# CAR_phase_1_schematic_design.net
KiCad netlist of a schematic drawn in EAGLE
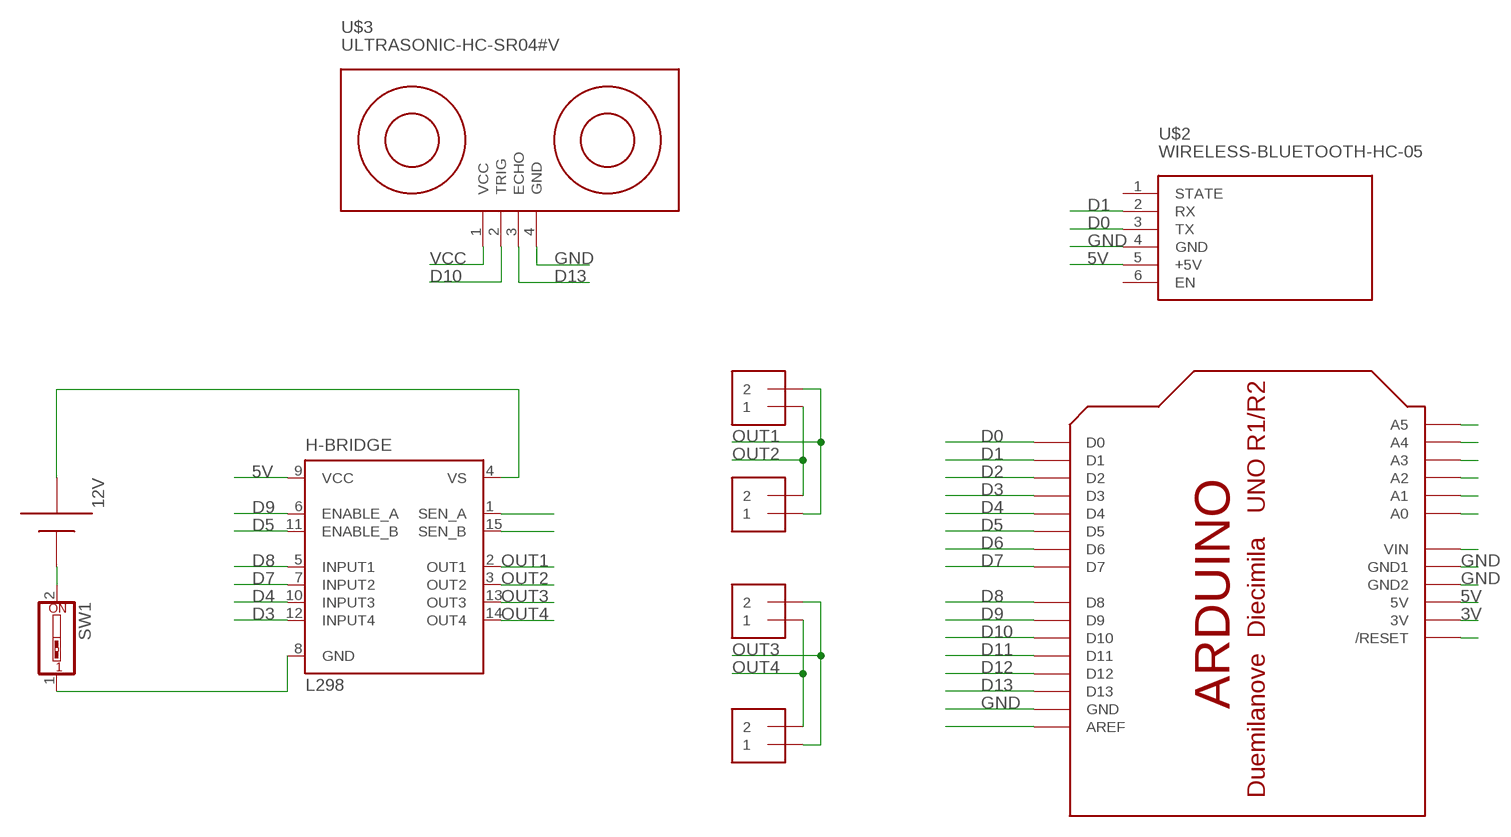
[diagram p0: schematic, sheet 1]

(export (version "E")
  (design (tool "Eeschema 10.0.6"))
  (components
    (comp (ref "12V")
      (value "AAA")
      (footprint "eagle-import:12BH412")
      (libsource (lib "eagle-import") (part "AAA"))
    )
    (comp (ref "H-BRIDGE")
      (value "L298")
      (footprint "eagle-import:MULTIWATT-15")
      (fields (field (name "MPN") "L298N"))
      (libsource (lib "eagle-import") (part "L298"))
    )
    (comp (ref "MOTOA1")
      (value "1X2-3.5MM")
      (footprint "eagle-import:1X2-3.5MM")
      (libsource (lib "eagle-import") (part "1X2-3.5MM"))
    )
    (comp (ref "MOTORA2")
      (value "1X2-3.5MM")
      (footprint "eagle-import:1X2-3.5MM")
      (libsource (lib "eagle-import") (part "1X2-3.5MM"))
    )
    (comp (ref "MOTORB1")
      (value "1X2-3.5MM")
      (footprint "eagle-import:1X2-3.5MM")
      (libsource (lib "eagle-import") (part "1X2-3.5MM"))
    )
    (comp (ref "MOTORB2")
      (value "1X2-3.5MM")
      (footprint "eagle-import:1X2-3.5MM")
      (libsource (lib "eagle-import") (part "1X2-3.5MM"))
    )
    (comp (ref "SW1")
      (value "SW_DIP-1")
      (footprint "eagle-import:EDG-01")
      (libsource (lib "eagle-import") (part "SW_DIP-1"))
    )
    (comp (ref "U$1")
      (value "ARDUINO-NOHOLE")
      (footprint "eagle-import:ARDUINO-NOHOLE")
      (libsource (lib "eagle-import") (part "ARDUINO-NOHOLE"))
    )
    (comp (ref "U$2")
      (value "WIRELESS-BLUETOOTH-HC-05")
      (footprint "eagle-import:WIRELESS-BLUETOOTH-HC-05")
      (libsource (lib "eagle-import") (part "WIRELESS-BLUETOOTH-HC-05"))
    )
    (comp (ref "U$3")
      (value "ULTRASONIC-HC-SR04#V")
      (footprint "eagle-import:ULTRASONIC-HC-SR04#V")
      (libsource (lib "eagle-import") (part "ULTRASONIC-HC-SR04#V"))
    )
  )
  (nets
    (net (code "1") (name "/3V") (class "Default")
      (node (ref "U$1") (pin "3V") (pinfunction "3V_3V") (pintype "power_in"))
    )
    (net (code "2") (name "/5V") (class "Default")
      (node (ref "H-BRIDGE") (pin "9") (pinfunction "VCC_9") (pintype "power_in"))
      (node (ref "U$1") (pin "5V") (pinfunction "5V_5V") (pintype "power_in"))
      (node (ref "U$2") (pin "5") (pinfunction "+5V_5") (pintype "power_in"))
    )
    (net (code "3") (name "/D0") (class "Default")
      (node (ref "U$1") (pin "D0") (pinfunction "D0_D0") (pintype "bidirectional"))
      (node (ref "U$2") (pin "3") (pinfunction "TX_3") (pintype "bidirectional"))
    )
    (net (code "4") (name "/D1") (class "Default")
      (node (ref "U$1") (pin "D1") (pinfunction "D1_D1") (pintype "bidirectional"))
      (node (ref "U$2") (pin "2") (pinfunction "RX_2") (pintype "bidirectional"))
    )
    (net (code "5") (name "/D2") (class "Default")
      (node (ref "U$1") (pin "D2") (pinfunction "D2_D2") (pintype "bidirectional"))
    )
    (net (code "6") (name "/D3") (class "Default")
      (node (ref "H-BRIDGE") (pin "12") (pinfunction "INPUT4_12") (pintype "input"))
      (node (ref "U$1") (pin "D3") (pinfunction "D3_D3") (pintype "bidirectional"))
    )
    (net (code "7") (name "/D4") (class "Default")
      (node (ref "H-BRIDGE") (pin "10") (pinfunction "INPUT3_10") (pintype "input"))
      (node (ref "U$1") (pin "D4") (pinfunction "D4_D4") (pintype "bidirectional"))
    )
    (net (code "8") (name "/D5") (class "Default")
      (node (ref "H-BRIDGE") (pin "11") (pinfunction "ENABLE_B_11") (pintype "input"))
      (node (ref "U$1") (pin "D5") (pinfunction "D5_D5") (pintype "bidirectional"))
    )
    (net (code "9") (name "/D6") (class "Default")
      (node (ref "U$1") (pin "D6") (pinfunction "D6_D6") (pintype "bidirectional"))
    )
    (net (code "10") (name "/D7") (class "Default")
      (node (ref "H-BRIDGE") (pin "7") (pinfunction "INPUT2_7") (pintype "input"))
      (node (ref "U$1") (pin "D7") (pinfunction "D7_D7") (pintype "bidirectional"))
    )
    (net (code "11") (name "/D8") (class "Default")
      (node (ref "H-BRIDGE") (pin "5") (pinfunction "INPUT1_5") (pintype "input"))
      (node (ref "U$1") (pin "D8") (pinfunction "D8_D8") (pintype "bidirectional"))
    )
    (net (code "12") (name "/D9") (class "Default")
      (node (ref "H-BRIDGE") (pin "6") (pinfunction "ENABLE_A_6") (pintype "input"))
      (node (ref "U$1") (pin "D9") (pinfunction "D9_D9") (pintype "bidirectional"))
    )
    (net (code "13") (name "/D10") (class "Default")
      (node (ref "U$1") (pin "D10") (pinfunction "D10_D10") (pintype "bidirectional"))
      (node (ref "U$3") (pin "2") (pinfunction "TRIG_2") (pintype "input"))
    )
    (net (code "14") (name "/D11") (class "Default")
      (node (ref "U$1") (pin "D11") (pinfunction "D11_D11") (pintype "bidirectional"))
    )
    (net (code "15") (name "/D12") (class "Default")
      (node (ref "U$1") (pin "D12") (pinfunction "D12_D12") (pintype "bidirectional"))
    )
    (net (code "16") (name "/D13") (class "Default")
      (node (ref "U$1") (pin "D13") (pinfunction "D13_D13") (pintype "bidirectional"))
      (node (ref "U$3") (pin "3") (pinfunction "ECHO_3") (pintype "output"))
    )
    (net (code "17") (name "/GND") (class "Default")
      (node (ref "U$1") (pin "GND") (pinfunction "GND_GND") (pintype "power_in"))
      (node (ref "U$1") (pin "GND1") (pinfunction "GND1_GND1") (pintype "power_in"))
      (node (ref "U$1") (pin "GND2") (pinfunction "GND2_GND2") (pintype "power_in"))
      (node (ref "U$2") (pin "4") (pinfunction "GND_4") (pintype "power_in"))
      (node (ref "U$3") (pin "4") (pinfunction "GND_4") (pintype "power_in"))
    )
    (net (code "18") (name "/OUT1") (class "Default")
      (node (ref "H-BRIDGE") (pin "2") (pinfunction "OUT1_2") (pintype "output"))
      (node (ref "MOTOA1") (pin "2") (pinfunction "2_2") (pintype "passive"))
      (node (ref "MOTORA2") (pin "1") (pinfunction "1_1") (pintype "passive"))
    )
    (net (code "19") (name "/OUT2") (class "Default")
      (node (ref "H-BRIDGE") (pin "3") (pinfunction "OUT2_3") (pintype "output"))
      (node (ref "MOTOA1") (pin "1") (pinfunction "1_1") (pintype "passive"))
      (node (ref "MOTORA2") (pin "2") (pinfunction "2_2") (pintype "passive"))
    )
    (net (code "20") (name "/OUT3") (class "Default")
      (node (ref "H-BRIDGE") (pin "13") (pinfunction "OUT3_13") (pintype "output"))
      (node (ref "MOTORB1") (pin "2") (pinfunction "2_2") (pintype "passive"))
      (node (ref "MOTORB2") (pin "1") (pinfunction "1_1") (pintype "passive"))
    )
    (net (code "21") (name "/OUT4") (class "Default")
      (node (ref "H-BRIDGE") (pin "14") (pinfunction "OUT4_14") (pintype "output"))
      (node (ref "MOTORB1") (pin "1") (pinfunction "1_1") (pintype "passive"))
      (node (ref "MOTORB2") (pin "2") (pinfunction "2_2") (pintype "passive"))
    )
    (net (code "22") (name "/VCC") (class "Default")
      (node (ref "U$3") (pin "1") (pinfunction "VCC_1") (pintype "power_in"))
    )
    (net (code "23") (name "Net-(12V-Pad+)") (class "Default")
      (node (ref "12V") (pin "+") (pinfunction "+_+") (pintype "bidirectional"))
      (node (ref "SW1") (pin "2") (pinfunction "2_2") (pintype "passive"))
    )
    (net (code "24") (name "Net-(H-BRIDGE-GND)") (class "Default")
      (node (ref "H-BRIDGE") (pin "8") (pinfunction "GND_8") (pintype "power_in"))
      (node (ref "SW1") (pin "1") (pinfunction "1_1") (pintype "passive"))
    )
    (net (code "25") (name "Net-(H-BRIDGE-VS)") (class "Default")
      (node (ref "12V") (pin "-") (pinfunction "-_-") (pintype "bidirectional"))
      (node (ref "H-BRIDGE") (pin "4") (pinfunction "VS_4") (pintype "power_in"))
    )
    (net (code "26") (name "unconnected-(H-BRIDGE-SEN_A-Pad1)") (class "Default")
      (node (ref "H-BRIDGE") (pin "1") (pinfunction "SEN_A_1") (pintype "input"))
    )
    (net (code "27") (name "unconnected-(H-BRIDGE-SEN_B-Pad15)") (class "Default")
      (node (ref "H-BRIDGE") (pin "15") (pinfunction "SEN_B_15") (pintype "input"))
    )
    (net (code "28") (name "unconnected-(U$1-PadA0)") (class "Default")
      (node (ref "U$1") (pin "A0") (pinfunction "A0_A0") (pintype "bidirectional"))
    )
    (net (code "29") (name "unconnected-(U$1-PadA1)") (class "Default")
      (node (ref "U$1") (pin "A1") (pinfunction "A1_A1") (pintype "bidirectional"))
    )
    (net (code "30") (name "unconnected-(U$1-PadA2)") (class "Default")
      (node (ref "U$1") (pin "A2") (pinfunction "A2_A2") (pintype "bidirectional"))
    )
    (net (code "31") (name "unconnected-(U$1-PadA3)") (class "Default")
      (node (ref "U$1") (pin "A3") (pinfunction "A3_A3") (pintype "bidirectional"))
    )
    (net (code "32") (name "unconnected-(U$1-PadA4)") (class "Default")
      (node (ref "U$1") (pin "A4") (pinfunction "A4_A4") (pintype "bidirectional"))
    )
    (net (code "33") (name "unconnected-(U$1-PadA5)") (class "Default")
      (node (ref "U$1") (pin "A5") (pinfunction "A5_A5") (pintype "bidirectional"))
    )
    (net (code "34") (name "unconnected-(U$1-PadAREF)") (class "Default")
      (node (ref "U$1") (pin "AREF") (pinfunction "AREF_AREF") (pintype "bidirectional"))
    )
    (net (code "35") (name "unconnected-(U$1-PadVIN)") (class "Default")
      (node (ref "U$1") (pin "VIN") (pinfunction "VIN_VIN") (pintype "power_in"))
    )
    (net (code "36") (name "unconnected-(U$1-{slash}RESET-PadRESET)") (class "Default")
      (node (ref "U$1") (pin "RESET") (pinfunction "/RESET_RESET") (pintype "bidirectional"))
    )
    (net (code "37") (name "unconnected-(U$2-EN-Pad6)") (class "Default")
      (node (ref "U$2") (pin "6") (pinfunction "EN_6") (pintype "bidirectional"))
    )
    (net (code "38") (name "unconnected-(U$2-STATE-Pad1)") (class "Default")
      (node (ref "U$2") (pin "1") (pinfunction "STATE_1") (pintype "bidirectional"))
    )
  )
)
